# MCU_IO.net
KiCad netlist of a schematic drawn in Altium Designer
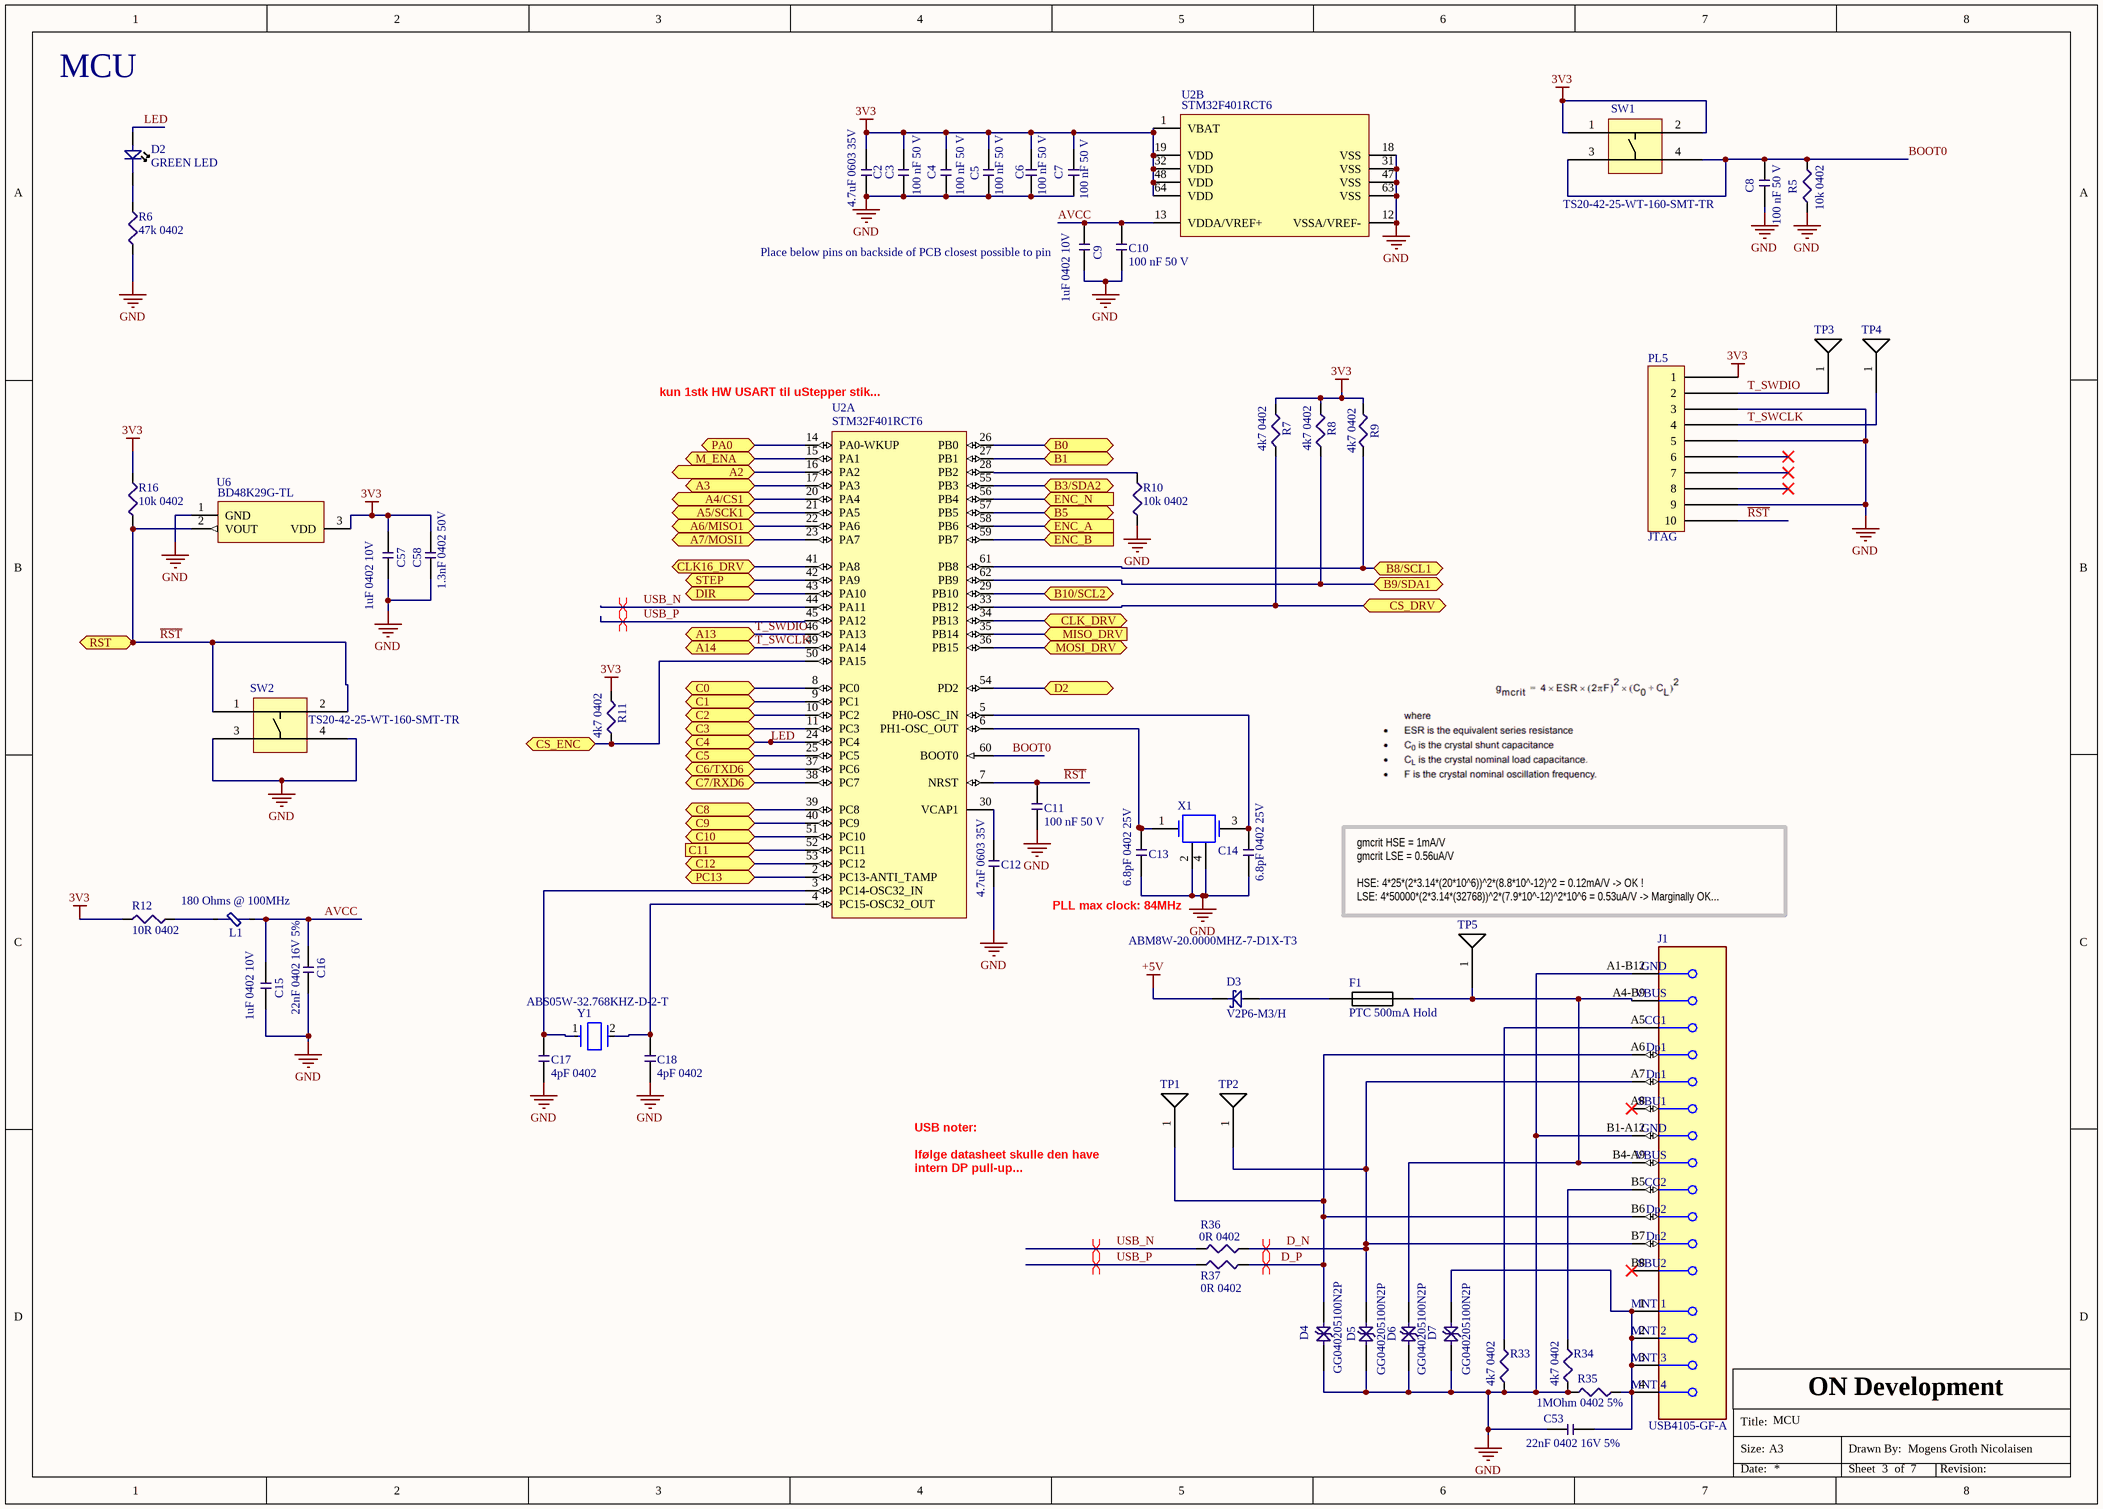
[diagram p0: MCU+IO.SchDoc]

(export (version "E")
  (design (tool "Eeschema 10.0.6"))
  (components
    (comp (ref "C2")
      (value "4.7uF 0603 35V")
      (footprint "CAP_0603")
      (fields (field (name "TOLERANCE") "10%"))
      (libsource (lib "ON Development Vault") (part "Capacitor"))
    )
    (comp (ref "C3")
      (value "100 nF 50 V")
      (footprint "CAP_0402")
      (description "Multilayer Ceramic Capacitors MLCC - SMD/SMT .1uF 50Volts X7R +/-10% 0402 STD")
      (fields (field (name "TOLERANCE") "10%") (field (name "VOLTAGE") "50 V"))
      (libsource (lib "ON Development Vault") (part "Capacitor"))
    )
    (comp (ref "C4")
      (value "100 nF 50 V")
      (footprint "CAP_0402")
      (description "Multilayer Ceramic Capacitors MLCC - SMD/SMT .1uF 50Volts X7R +/-10% 0402 STD")
      (fields (field (name "TOLERANCE") "10%") (field (name "VOLTAGE") "50 V"))
      (libsource (lib "ON Development Vault") (part "Capacitor"))
    )
    (comp (ref "C5")
      (value "100 nF 50 V")
      (footprint "CAP_0402")
      (description "Multilayer Ceramic Capacitors MLCC - SMD/SMT .1uF 50Volts X7R +/-10% 0402 STD")
      (fields (field (name "TOLERANCE") "10%") (field (name "VOLTAGE") "50 V"))
      (libsource (lib "ON Development Vault") (part "Capacitor"))
    )
    (comp (ref "C6")
      (value "100 nF 50 V")
      (footprint "CAP_0402")
      (description "Multilayer Ceramic Capacitors MLCC - SMD/SMT .1uF 50Volts X7R +/-10% 0402 STD")
      (fields (field (name "TOLERANCE") "10%") (field (name "VOLTAGE") "50 V"))
      (libsource (lib "ON Development Vault") (part "Capacitor"))
    )
    (comp (ref "C7")
      (value "100 nF 50 V")
      (footprint "CAP_0402")
      (description "Multilayer Ceramic Capacitors MLCC - SMD/SMT .1uF 50Volts X7R +/-10% 0402 STD")
      (fields (field (name "TOLERANCE") "10%") (field (name "VOLTAGE") "50 V"))
      (libsource (lib "ON Development Vault") (part "Capacitor"))
    )
    (comp (ref "C8")
      (value "100 nF 50 V")
      (footprint "CAP_0402")
      (description "Multilayer Ceramic Capacitors MLCC - SMD/SMT .1uF 50Volts X7R +/-10% 0402 STD")
      (fields (field (name "TOLERANCE") "10%") (field (name "VOLTAGE") "50 V"))
      (libsource (lib "ON Development Vault") (part "Capacitor"))
    )
    (comp (ref "C9")
      (value "1uF 0402 10V")
      (footprint "CAP_0402")
      (description "1uF 0402 10V 10% X5R")
      (fields (field (name "TOLERANCE") "10%") (field (name "VOLTAGE") "10 V"))
      (libsource (lib "ON Development Vault") (part "Capacitor"))
    )
    (comp (ref "C10")
      (value "100 nF 50 V")
      (footprint "CAP_0402")
      (description "Multilayer Ceramic Capacitors MLCC - SMD/SMT .1uF 50Volts X7R +/-10% 0402 STD")
      (fields (field (name "TOLERANCE") "10%") (field (name "VOLTAGE") "50 V"))
      (libsource (lib "ON Development Vault") (part "Capacitor"))
    )
    (comp (ref "C11")
      (value "100 nF 50 V")
      (footprint "CAP_0402")
      (description "Multilayer Ceramic Capacitors MLCC - SMD/SMT .1uF 50Volts X7R +/-10% 0402 STD")
      (fields (field (name "TOLERANCE") "10%") (field (name "VOLTAGE") "50 V"))
      (libsource (lib "ON Development Vault") (part "Capacitor"))
    )
    (comp (ref "C12")
      (value "4.7uF 0603 35V")
      (footprint "CAP_0603")
      (fields (field (name "TOLERANCE") "10%"))
      (libsource (lib "ON Development Vault") (part "Capacitor"))
    )
    (comp (ref "C13")
      (value "6.8pF 0402 25V")
      (footprint "CAP_0402")
      (description "Multilayer Ceramic Capacitors MLCC - SMD/SMT 0402 6.8pF 25volts C0G +/-0.25pF")
      (fields (field (name "VOLTAGE") "25V") (field (name "MANUFACTURER PART NO.") "GRM1555C1E6R8CA01D"))
      (libsource (lib "ON Development Vault") (part "Capacitor"))
    )
    (comp (ref "C14")
      (value "6.8pF 0402 25V")
      (footprint "CAP_0402")
      (description "Multilayer Ceramic Capacitors MLCC - SMD/SMT 0402 6.8pF 25volts C0G +/-0.25pF")
      (fields (field (name "VOLTAGE") "25V") (field (name "MANUFACTURER PART NO.") "GRM1555C1E6R8CA01D"))
      (libsource (lib "ON Development Vault") (part "Capacitor"))
    )
    (comp (ref "C15")
      (value "1uF 0402 10V")
      (footprint "CAP_0402")
      (description "1uF 0402 10V 10% X5R")
      (fields (field (name "TOLERANCE") "10%") (field (name "VOLTAGE") "10 V"))
      (libsource (lib "ON Development Vault") (part "Capacitor"))
    )
    (comp (ref "C16")
      (value "22nF 0402 16V 5%")
      (footprint "CAP_0402")
      (description "22nF 0402 16V X7R 5%")
      (fields (field (name "TOLERANCE") "5%") (field (name "VOLTAGE") "16V"))
      (libsource (lib "ON Development Vault") (part "Capacitor"))
    )
    (comp (ref "C17")
      (value "4pF 0402")
      (footprint "CAP_0402")
      (description "GJM1555C1HR40BB01D ; Rohs; Murata ; Cap Ceramic 0.4PF 50V C0G 0402")
      (fields (field (name "TOLERANCE") "0.1pF") (field (name "VOLTAGE") "50V"))
      (libsource (lib "ON Development Vault") (part "Capacitor"))
    )
    (comp (ref "C18")
      (value "4pF 0402")
      (footprint "CAP_0402")
      (description "GJM1555C1HR40BB01D ; Rohs; Murata ; Cap Ceramic 0.4PF 50V C0G 0402")
      (fields (field (name "TOLERANCE") "0.1pF") (field (name "VOLTAGE") "50V"))
      (libsource (lib "ON Development Vault") (part "Capacitor"))
    )
    (comp (ref "C53")
      (value "22nF 0402 16V 5%")
      (footprint "CAP_0402")
      (description "22nF 0402 16V X7R 5%")
      (fields (field (name "TOLERANCE") "5%") (field (name "VOLTAGE") "16V"))
      (libsource (lib "ON Development Vault") (part "Capacitor"))
    )
    (comp (ref "C57")
      (value "1uF 0402 10V")
      (footprint "CAP_0402")
      (description "1uF 0402 10V 10% X5R")
      (fields (field (name "TOLERANCE") "10%") (field (name "VOLTAGE") "10 V"))
      (libsource (lib "ON Development Vault") (part "Capacitor"))
    )
    (comp (ref "C58")
      (value "1.3nF 0402 50V")
      (footprint "CAP_0402")
      (description "Cap Ceramic 0.0013uF 50V C0G 5% SMD 0402 125°C Paper T/R")
      (fields (field (name "TOLERANCE") "10%") (field (name "VOLTAGE") "50V"))
      (libsource (lib "ON Development Vault") (part "Capacitor"))
    )
    (comp (ref "D2")
      (value "GREEN LED")
      (footprint "0402 LED")
      (description "0402 SMD LED")
      (fields (field (name "MFG. PART NUMBER") "LTST-C281KGKT"))
      (libsource (lib "ON Development Vault") (part "LED"))
    )
    (comp (ref "D3")
      (value "V2P6-M3/H")
      (footprint "MicroSMP")
      (description "DIODE SCHOTTKY 60V 2A MICROSMP")
      (libsource (lib "ON Development Vault") (part "Schottky"))
    )
    (comp (ref "D4")
      (value "TVS")
      (footprint "RES_0402")
      (description "TVS DIODE 12VC 8A IPP 0402")
      (fields (field (name "MFG. PART NUMBER") "GG040205100N2P"))
      (libsource (lib "ON Development Vault") (part "TVS"))
    )
    (comp (ref "D5")
      (value "TVS")
      (footprint "RES_0402")
      (description "TVS DIODE 12VC 8A IPP 0402")
      (fields (field (name "MFG. PART NUMBER") "GG040205100N2P"))
      (libsource (lib "ON Development Vault") (part "TVS"))
    )
    (comp (ref "D6")
      (value "TVS")
      (footprint "RES_0402")
      (description "TVS DIODE 12VC 8A IPP 0402")
      (fields (field (name "MFG. PART NUMBER") "GG040205100N2P"))
      (libsource (lib "ON Development Vault") (part "TVS"))
    )
    (comp (ref "D7")
      (value "TVS")
      (footprint "RES_0402")
      (description "TVS DIODE 12VC 8A IPP 0402")
      (fields (field (name "MFG. PART NUMBER") "GG040205100N2P"))
      (libsource (lib "ON Development Vault") (part "TVS"))
    )
    (comp (ref "F1")
      (value "PTC 500mA Hold")
      (footprint "PTC Fuse 1206")
      (description "PTC RESET FUSE 8V 500MA 1206")
      (fields (field (name "MFG. PART NUMBER") "0ZCJ0050FF2G"))
      (libsource (lib "ON Development Vault") (part "Fuse"))
    )
    (comp (ref "J1")
      (value "USB4105-GF-A")
      (footprint "FP-USB4105-GF-A-MFG")
      (description "Conn USB 2.0 Type C RCP 24 POS 0.3mm/0.5mm Solder RA SMD 24 Terminal 1 Port T/R")
      (libsource (lib "ON Development Vault") (part "e7c17a616881a82b79941196b4bec10"))
    )
    (comp (ref "L1")
      (value "180 Ohms @ 100MHz")
      (footprint "IND_0603")
      (description "FERRITE BEAD 180 OHM 0603 1LN")
      (fields (field (name "MFG. PART NUMBER") "BLM18PG181SN1D"))
      (libsource (lib "ON Development Vault") (part "Ferrite"))
    )
    (comp (ref "PL5")
      (value "JTAG")
      (footprint "FP-62101021021-MFG")
      (description "Conn, Header, 10Pos, 2Row, 1.27Mm Rohs Compliant: Yes")
      (libsource (lib "ON Development Vault") (part "10-pin header"))
    )
    (comp (ref "R5")
      (value "10k 0402")
      (footprint "RES_0402")
      (description "RES SMD 10K OHM 1% 1/16W 0402")
      (fields (field (name "POWER") "1/16 W") (field (name "TOLERANCE") "1 %"))
      (libsource (lib "ON Development Vault") (part "Resistor"))
    )
    (comp (ref "R6")
      (value "47k 0402")
      (footprint "RES_0402")
      (description "RES SMD 47K OHM 1% 1/16W 0402")
      (fields (field (name "POWER") "1/16W") (field (name "TOLERANCE") "1%"))
      (libsource (lib "ON Development Vault") (part "Resistor"))
    )
    (comp (ref "R7")
      (value "4k7 0402")
      (footprint "RES_0402")
      (description "RES SMD 4.7K OHM 1% 1/16W 0402")
      (fields (field (name "POWER") "1/16W") (field (name "TOLERANCE") "1"))
      (libsource (lib "ON Development Vault") (part "Resistor"))
    )
    (comp (ref "R8")
      (value "4k7 0402")
      (footprint "RES_0402")
      (description "RES SMD 4.7K OHM 1% 1/16W 0402")
      (fields (field (name "POWER") "1/16W") (field (name "TOLERANCE") "1"))
      (libsource (lib "ON Development Vault") (part "Resistor"))
    )
    (comp (ref "R9")
      (value "4k7 0402")
      (footprint "RES_0402")
      (description "RES SMD 4.7K OHM 1% 1/16W 0402")
      (fields (field (name "POWER") "1/16W") (field (name "TOLERANCE") "1"))
      (libsource (lib "ON Development Vault") (part "Resistor"))
    )
    (comp (ref "R10")
      (value "10k 0402")
      (footprint "RES_0402")
      (description "RES SMD 10K OHM 1% 1/16W 0402")
      (fields (field (name "POWER") "1/16 W") (field (name "TOLERANCE") "1 %"))
      (libsource (lib "ON Development Vault") (part "Resistor"))
    )
    (comp (ref "R11")
      (value "4k7 0402")
      (footprint "RES_0402")
      (description "RES SMD 4.7K OHM 1% 1/16W 0402")
      (fields (field (name "POWER") "1/16W") (field (name "TOLERANCE") "1"))
      (libsource (lib "ON Development Vault") (part "Resistor"))
    )
    (comp (ref "R12")
      (value "10R 0402")
      (footprint "RES_0402")
      (description "RES SMD 10 OHM 1% 1/16W 0402")
      (fields (field (name "POWER") "63mW") (field (name "TOLERANCE") "1%"))
      (libsource (lib "ON Development Vault") (part "Resistor"))
    )
    (comp (ref "R16")
      (value "10k 0402")
      (footprint "RES_0402")
      (description "RES SMD 10K OHM 1% 1/16W 0402")
      (fields (field (name "POWER") "1/16 W") (field (name "TOLERANCE") "1 %"))
      (libsource (lib "ON Development Vault") (part "Resistor"))
    )
    (comp (ref "R33")
      (value "4k7 0402")
      (footprint "RES_0402")
      (description "RES SMD 4.7K OHM 1% 1/16W 0402")
      (fields (field (name "POWER") "1/16W") (field (name "TOLERANCE") "1"))
      (libsource (lib "ON Development Vault") (part "Resistor"))
    )
    (comp (ref "R34")
      (value "4k7 0402")
      (footprint "RES_0402")
      (description "RES SMD 4.7K OHM 1% 1/16W 0402")
      (fields (field (name "POWER") "1/16W") (field (name "TOLERANCE") "1"))
      (libsource (lib "ON Development Vault") (part "Resistor"))
    )
    (comp (ref "R35")
      (value "1MOhm 0402 5%")
      (footprint "RES_0402")
      (description "RES SMD 1M OHM 5% 1/16W 0402")
      (fields (field (name "POWER") "1/16 W") (field (name "TOLERANCE") "5%"))
      (libsource (lib "ON Development Vault") (part "Resistor"))
    )
    (comp (ref "R36")
      (value "0R 0402")
      (footprint "RES_0402")
      (description "RES SMD 0 OHM 1/16W 0402")
      (fields (field (name "POWER") "63mW") (field (name "MFG. PART NUMBER") "RC0402JR-070RL"))
      (libsource (lib "ON Development Vault") (part "Resistor"))
    )
    (comp (ref "R37")
      (value "0R 0402")
      (footprint "RES_0402")
      (description "RES SMD 0 OHM 1/16W 0402")
      (fields (field (name "POWER") "63mW") (field (name "MFG. PART NUMBER") "RC0402JR-070RL"))
      (libsource (lib "ON Development Vault") (part "Resistor"))
    )
    (comp (ref "SW1")
      (value "TS20-42-25-WT-160-SMT-TR")
      (footprint "TS20-42-25-WT-160-SMT-TR-Footprint-1")
      (description "Tactile Switch SPST-NO Top Actuated Surface Mount")
      (libsource (lib "ON Development Vault") (part "PTS540"))
    )
    (comp (ref "SW2")
      (value "TS20-42-25-WT-160-SMT-TR")
      (footprint "TS20-42-25-WT-160-SMT-TR-Footprint-1")
      (description "Tactile Switch SPST-NO Top Actuated Surface Mount")
      (libsource (lib "ON Development Vault") (part "PTS540"))
    )
    (comp (ref "TP1")
      (value "TestPoint")
      (footprint "1x0mm")
      (description "Testpoint")
      (libsource (lib "ON Development Vault") (part "Testpoint"))
    )
    (comp (ref "TP2")
      (value "TestPoint")
      (footprint "1x0mm")
      (description "Testpoint")
      (libsource (lib "ON Development Vault") (part "Testpoint"))
    )
    (comp (ref "TP3")
      (value "TestPoint")
      (footprint "1x0mm")
      (description "Testpoint")
      (libsource (lib "ON Development Vault") (part "Testpoint"))
    )
    (comp (ref "TP4")
      (value "TestPoint")
      (footprint "1x0mm")
      (description "Testpoint")
      (libsource (lib "ON Development Vault") (part "Testpoint"))
    )
    (comp (ref "TP5")
      (value "TestPoint")
      (footprint "1x0mm")
      (description "Testpoint")
      (libsource (lib "ON Development Vault") (part "Testpoint"))
    )
    (comp (ref "U2")
      (value "STM32F401RCT6")
      (footprint "STM-LQFP64_M")
      (description "ARM® Cortex®-M4 STM32 F4 Microcontroller IC 32-Bit 84MHz 256KB (256K x 8) FLASH")
      (libsource (lib "ON Development Vault") (part "MC-ARM-STM32F401-SQ64"))
    )
    (comp (ref "U6")
      (value "Supervisor")
      (footprint "SOT95P282X125-3N")
      (description "IC DETECTOR VOLT 2.9V OD SSOP3")
      (fields (field (name "MANUFACTURER PART NO.:") "BD48K29G-TL"))
      (libsource (lib "ON Development Vault") (part "BD48K29G-TL-Symbol-1"))
    )
    (comp (ref "X1")
      (value "ABM8W-20.0000MHZ-7-D1X-T3")
      (footprint "3.2x2.5mm 4pin xtal")
      (description "Crystal 20MHz ±10ppm (Tol) ±20ppm (Stability) 7pF FUND 50Ohm 4-Pin SMD T/R")
      (libsource (lib "ON Development Vault") (part "TSX-3225 20MHZ"))
    )
    (comp (ref "Y1")
      (value "ABS05W-32.768KHZ-D-2-T")
      (footprint "FP-ABS05W-MFG")
      (description "ABS05W IoT Optimized Crystal 32.768KHz 4pF 70K Ohm ±20ppm 2-Pin SMD T/R")
      (libsource (lib "ON Development Vault") (part "c23a69dc6c9e2f18f2079038eb95dd1"))
    )
  )
  (nets
    (net (code "1") (name "+5V") (class "Default")
      (node (ref "D3") (pin "2") (pinfunction "2_2") (pintype "passive"))
    )
    (net (code "2") (name "/A2") (class "Default")
      (node (ref "U2") (pin "16") (pinfunction "PA2_16") (pintype "bidirectional"))
    )
    (net (code "3") (name "/A3") (class "Default")
      (node (ref "U2") (pin "17") (pinfunction "PA3_17") (pintype "bidirectional"))
    )
    (net (code "4") (name "/A4{slash}CS1") (class "Default")
      (node (ref "U2") (pin "20") (pinfunction "PA4_20") (pintype "bidirectional"))
    )
    (net (code "5") (name "/A5{slash}SCK1") (class "Default")
      (node (ref "U2") (pin "21") (pinfunction "PA5_21") (pintype "bidirectional"))
    )
    (net (code "6") (name "/A6{slash}MISO1") (class "Default")
      (node (ref "U2") (pin "22") (pinfunction "PA6_22") (pintype "bidirectional"))
    )
    (net (code "7") (name "/A7{slash}MOSI1") (class "Default")
      (node (ref "U2") (pin "23") (pinfunction "PA7_23") (pintype "bidirectional"))
    )
    (net (code "8") (name "/AVCC") (class "Default")
      (node (ref "C10") (pin "2") (pinfunction "2_2") (pintype "passive"))
      (node (ref "C15") (pin "2") (pinfunction "2_2") (pintype "passive"))
      (node (ref "C16") (pin "2") (pinfunction "2_2") (pintype "passive"))
      (node (ref "C9") (pin "2") (pinfunction "2_2") (pintype "passive"))
      (node (ref "L1") (pin "2") (pinfunction "2_2") (pintype "passive"))
      (node (ref "U2") (pin "13") (pinfunction "VDDA/VREF+_13") (pintype "power_in"))
    )
    (net (code "9") (name "/B0") (class "Default")
      (node (ref "U2") (pin "26") (pinfunction "PB0_26") (pintype "bidirectional"))
    )
    (net (code "10") (name "/B1") (class "Default")
      (node (ref "U2") (pin "27") (pinfunction "PB1_27") (pintype "bidirectional"))
    )
    (net (code "11") (name "/B3{slash}SDA2") (class "Default")
      (node (ref "U2") (pin "55") (pinfunction "PB3_55") (pintype "bidirectional"))
    )
    (net (code "12") (name "/B5") (class "Default")
      (node (ref "U2") (pin "57") (pinfunction "PB5_57") (pintype "bidirectional"))
    )
    (net (code "13") (name "/B8{slash}SCL1") (class "Default")
      (node (ref "R9") (pin "1") (pinfunction "1_1") (pintype "passive"))
      (node (ref "U2") (pin "61") (pinfunction "PB8_61") (pintype "bidirectional"))
    )
    (net (code "14") (name "/B9{slash}SDA1") (class "Default")
      (node (ref "R8") (pin "1") (pinfunction "1_1") (pintype "passive"))
      (node (ref "U2") (pin "62") (pinfunction "PB9_62") (pintype "bidirectional"))
    )
    (net (code "15") (name "/B10{slash}SCL2") (class "Default")
      (node (ref "U2") (pin "29") (pinfunction "PB10_29") (pintype "bidirectional"))
    )
    (net (code "16") (name "/BOOT0") (class "Default")
      (node (ref "C8") (pin "2") (pinfunction "2_2") (pintype "passive"))
      (node (ref "R5") (pin "2") (pinfunction "2_2") (pintype "passive"))
      (node (ref "SW1") (pin "3") (pinfunction "3_3") (pintype "passive"))
      (node (ref "SW1") (pin "4") (pinfunction "4_4") (pintype "passive"))
      (node (ref "U2") (pin "60") (pinfunction "BOOT0_60") (pintype "input"))
    )
    (net (code "17") (name "/C0") (class "Default")
      (node (ref "U2") (pin "8") (pinfunction "PC0_8") (pintype "bidirectional"))
    )
    (net (code "18") (name "/C1") (class "Default")
      (node (ref "U2") (pin "9") (pinfunction "PC1_9") (pintype "bidirectional"))
    )
    (net (code "19") (name "/C2") (class "Default")
      (node (ref "U2") (pin "10") (pinfunction "PC2_10") (pintype "bidirectional"))
    )
    (net (code "20") (name "/C3") (class "Default")
      (node (ref "U2") (pin "11") (pinfunction "PC3_11") (pintype "bidirectional"))
    )
    (net (code "21") (name "/C5") (class "Default")
      (node (ref "U2") (pin "25") (pinfunction "PC5_25") (pintype "bidirectional"))
    )
    (net (code "22") (name "/C6{slash}TXD6") (class "Default")
      (node (ref "U2") (pin "37") (pinfunction "PC6_37") (pintype "bidirectional"))
    )
    (net (code "23") (name "/C7{slash}RXD6") (class "Default")
      (node (ref "U2") (pin "38") (pinfunction "PC7_38") (pintype "bidirectional"))
    )
    (net (code "24") (name "/C8") (class "Default")
      (node (ref "U2") (pin "39") (pinfunction "PC8_39") (pintype "bidirectional"))
    )
    (net (code "25") (name "/C9") (class "Default")
      (node (ref "U2") (pin "40") (pinfunction "PC9_40") (pintype "bidirectional"))
    )
    (net (code "26") (name "/C10") (class "Default")
      (node (ref "U2") (pin "51") (pinfunction "PC10_51") (pintype "bidirectional"))
    )
    (net (code "27") (name "/C11") (class "Default")
      (node (ref "U2") (pin "52") (pinfunction "PC11_52") (pintype "bidirectional"))
    )
    (net (code "28") (name "/C12") (class "Default")
      (node (ref "U2") (pin "53") (pinfunction "PC12_53") (pintype "bidirectional"))
    )
    (net (code "29") (name "/CLK16_DRV") (class "Default")
      (node (ref "U2") (pin "41") (pinfunction "PA8_41") (pintype "bidirectional"))
    )
    (net (code "30") (name "/CLK_DRV") (class "Default")
      (node (ref "U2") (pin "34") (pinfunction "PB13_34") (pintype "bidirectional"))
    )
    (net (code "31") (name "/CS_DRV") (class "Default")
      (node (ref "R7") (pin "1") (pinfunction "1_1") (pintype "passive"))
      (node (ref "U2") (pin "33") (pinfunction "PB12_33") (pintype "bidirectional"))
    )
    (net (code "32") (name "/CS_ENC") (class "Default")
      (node (ref "R11") (pin "1") (pinfunction "1_1") (pintype "passive"))
      (node (ref "U2") (pin "50") (pinfunction "PA15_50") (pintype "bidirectional"))
    )
    (net (code "33") (name "/D2") (class "Default")
      (node (ref "U2") (pin "54") (pinfunction "PD2_54") (pintype "bidirectional"))
    )
    (net (code "34") (name "/DIR") (class "Default")
      (node (ref "U2") (pin "43") (pinfunction "PA10_43") (pintype "bidirectional"))
    )
    (net (code "35") (name "/D_N") (class "Default")
      (node (ref "D5") (pin "2") (pinfunction "Cathode_2") (pintype "passive"))
      (node (ref "J1") (pin "A7") (pinfunction "Dn1_A7") (pintype "bidirectional"))
      (node (ref "J1") (pin "B7") (pinfunction "Dn2_B7") (pintype "bidirectional"))
      (node (ref "R36") (pin "2") (pinfunction "2_2") (pintype "passive"))
      (node (ref "TP2") (pin "1") (pinfunction "0_1") (pintype "passive"))
    )
    (net (code "36") (name "/D_P") (class "Default")
      (node (ref "D4") (pin "2") (pinfunction "Cathode_2") (pintype "passive"))
      (node (ref "J1") (pin "A6") (pinfunction "Dp1_A6") (pintype "bidirectional"))
      (node (ref "J1") (pin "B6") (pinfunction "Dp2_B6") (pintype "bidirectional"))
      (node (ref "R37") (pin "2") (pinfunction "2_2") (pintype "passive"))
      (node (ref "TP1") (pin "1") (pinfunction "0_1") (pintype "passive"))
    )
    (net (code "37") (name "/ENC_A") (class "Default")
      (node (ref "U2") (pin "58") (pinfunction "PB6_58") (pintype "bidirectional"))
    )
    (net (code "38") (name "/ENC_B") (class "Default")
      (node (ref "U2") (pin "59") (pinfunction "PB7_59") (pintype "bidirectional"))
    )
    (net (code "39") (name "/ENC_N") (class "Default")
      (node (ref "U2") (pin "56") (pinfunction "PB4_56") (pintype "bidirectional"))
    )
    (net (code "40") (name "/LED") (class "Default")
      (node (ref "D2") (pin "1") (pinfunction "1_1") (pintype "passive"))
      (node (ref "U2") (pin "24") (pinfunction "PC4_24") (pintype "bidirectional"))
    )
    (net (code "41") (name "/MISO_DRV") (class "Default")
      (node (ref "U2") (pin "35") (pinfunction "PB14_35") (pintype "bidirectional"))
    )
    (net (code "42") (name "/MOSI_DRV") (class "Default")
      (node (ref "U2") (pin "36") (pinfunction "PB15_36") (pintype "bidirectional"))
    )
    (net (code "43") (name "/M_ENA") (class "Default")
      (node (ref "U2") (pin "15") (pinfunction "PA1_15") (pintype "bidirectional"))
    )
    (net (code "44") (name "/PA0") (class "Default")
      (node (ref "U2") (pin "14") (pinfunction "PA0-WKUP_14") (pintype "bidirectional"))
    )
    (net (code "45") (name "/PC13") (class "Default")
      (node (ref "U2") (pin "2") (pinfunction "PC13-ANTI_TAMP_2") (pintype "bidirectional"))
    )
    (net (code "46") (name "/STEP") (class "Default")
      (node (ref "U2") (pin "42") (pinfunction "PA9_42") (pintype "bidirectional"))
    )
    (net (code "47") (name "/T_SWCLK") (class "Default")
      (node (ref "PL5") (pin "4") (pinfunction "4_4") (pintype "passive"))
      (node (ref "TP4") (pin "1") (pinfunction "0_1") (pintype "passive"))
      (node (ref "U2") (pin "49") (pinfunction "PA14_49") (pintype "bidirectional"))
    )
    (net (code "48") (name "/T_SWDIO") (class "Default")
      (node (ref "PL5") (pin "2") (pinfunction "2_2") (pintype "passive"))
      (node (ref "TP3") (pin "1") (pinfunction "0_1") (pintype "passive"))
      (node (ref "U2") (pin "46") (pinfunction "PA13_46") (pintype "bidirectional"))
    )
    (net (code "49") (name "/USB_N") (class "Default")
      (node (ref "R36") (pin "1") (pinfunction "1_1") (pintype "passive"))
      (node (ref "U2") (pin "44") (pinfunction "PA11_44") (pintype "bidirectional"))
    )
    (net (code "50") (name "/USB_P") (class "Default")
      (node (ref "R37") (pin "1") (pinfunction "1_1") (pintype "passive"))
      (node (ref "U2") (pin "45") (pinfunction "PA12_45") (pintype "bidirectional"))
    )
    (net (code "51") (name "/~{RST}") (class "Default")
      (node (ref "C11") (pin "2") (pinfunction "2_2") (pintype "passive"))
      (node (ref "PL5") (pin "10") (pinfunction "10_10") (pintype "passive"))
      (node (ref "R16") (pin "1") (pinfunction "1_1") (pintype "passive"))
      (node (ref "SW2") (pin "1") (pinfunction "1_1") (pintype "passive"))
      (node (ref "SW2") (pin "2") (pinfunction "2_2") (pintype "passive"))
      (node (ref "U2") (pin "7") (pinfunction "NRST_7") (pintype "bidirectional"))
      (node (ref "U6") (pin "2") (pinfunction "VOUT_2") (pintype "output"))
    )
    (net (code "52") (name "3V3") (class "Default")
      (node (ref "C2") (pin "2") (pinfunction "2_2") (pintype "passive"))
      (node (ref "C3") (pin "2") (pinfunction "2_2") (pintype "passive"))
      (node (ref "C4") (pin "2") (pinfunction "2_2") (pintype "passive"))
      (node (ref "C5") (pin "2") (pinfunction "2_2") (pintype "passive"))
      (node (ref "C57") (pin "2") (pinfunction "2_2") (pintype "passive"))
      (node (ref "C58") (pin "2") (pinfunction "2_2") (pintype "passive"))
      (node (ref "C6") (pin "2") (pinfunction "2_2") (pintype "passive"))
      (node (ref "C7") (pin "2") (pinfunction "2_2") (pintype "passive"))
      (node (ref "PL5") (pin "1") (pinfunction "1_1") (pintype "passive"))
      (node (ref "R11") (pin "2") (pinfunction "2_2") (pintype "passive"))
      (node (ref "R12") (pin "1") (pinfunction "1_1") (pintype "passive"))
      (node (ref "R16") (pin "2") (pinfunction "2_2") (pintype "passive"))
      (node (ref "R7") (pin "2") (pinfunction "2_2") (pintype "passive"))
      (node (ref "R8") (pin "2") (pinfunction "2_2") (pintype "passive"))
      (node (ref "R9") (pin "2") (pinfunction "2_2") (pintype "passive"))
      (node (ref "SW1") (pin "1") (pinfunction "1_1") (pintype "passive"))
      (node (ref "SW1") (pin "2") (pinfunction "2_2") (pintype "passive"))
      (node (ref "U2") (pin "1") (pinfunction "VBAT_1") (pintype "power_in"))
      (node (ref "U2") (pin "19") (pinfunction "VDD_19") (pintype "power_in"))
      (node (ref "U2") (pin "32") (pinfunction "VDD_32") (pintype "power_in"))
      (node (ref "U2") (pin "48") (pinfunction "VDD_48") (pintype "power_in"))
      (node (ref "U2") (pin "64") (pinfunction "VDD_64") (pintype "power_in"))
      (node (ref "U6") (pin "3") (pinfunction "VDD_3") (pintype "power_in"))
    )
    (net (code "53") (name "GND") (class "Default")
      (node (ref "C10") (pin "1") (pinfunction "1_1") (pintype "passive"))
      (node (ref "C11") (pin "1") (pinfunction "1_1") (pintype "passive"))
      (node (ref "C12") (pin "1") (pinfunction "1_1") (pintype "passive"))
      (node (ref "C13") (pin "1") (pinfunction "1_1") (pintype "passive"))
      (node (ref "C14") (pin "1") (pinfunction "1_1") (pintype "passive"))
      (node (ref "C15") (pin "1") (pinfunction "1_1") (pintype "passive"))
      (node (ref "C16") (pin "1") (pinfunction "1_1") (pintype "passive"))
      (node (ref "C17") (pin "1") (pinfunction "1_1") (pintype "passive"))
      (node (ref "C18") (pin "1") (pinfunction "1_1") (pintype "passive"))
      (node (ref "C2") (pin "1") (pinfunction "1_1") (pintype "passive"))
      (node (ref "C3") (pin "1") (pinfunction "1_1") (pintype "passive"))
      (node (ref "C4") (pin "1") (pinfunction "1_1") (pintype "passive"))
      (node (ref "C5") (pin "1") (pinfunction "1_1") (pintype "passive"))
      (node (ref "C53") (pin "1") (pinfunction "1_1") (pintype "passive"))
      (node (ref "C57") (pin "1") (pinfunction "1_1") (pintype "passive"))
      (node (ref "C58") (pin "1") (pinfunction "1_1") (pintype "passive"))
      (node (ref "C6") (pin "1") (pinfunction "1_1") (pintype "passive"))
      (node (ref "C7") (pin "1") (pinfunction "1_1") (pintype "passive"))
      (node (ref "C8") (pin "1") (pinfunction "1_1") (pintype "passive"))
      (node (ref "C9") (pin "1") (pinfunction "1_1") (pintype "passive"))
      (node (ref "D4") (pin "1") (pinfunction "Anode_1") (pintype "passive"))
      (node (ref "D5") (pin "1") (pinfunction "Anode_1") (pintype "passive"))
      (node (ref "D6") (pin "1") (pinfunction "Anode_1") (pintype "passive"))
      (node (ref "D7") (pin "1") (pinfunction "Anode_1") (pintype "passive"))
      (node (ref "J1") (pin "A1-B12") (pinfunction "GND_A1-B12") (pintype "power_in"))
      (node (ref "J1") (pin "B1-A12") (pinfunction "GND_B1-A12") (pintype "bidirectional"))
      (node (ref "PL5") (pin "3") (pinfunction "3_3") (pintype "passive"))
      (node (ref "PL5") (pin "5") (pinfunction "5_5") (pintype "passive"))
      (node (ref "PL5") (pin "9") (pinfunction "9_9") (pintype "passive"))
      (node (ref "R10") (pin "1") (pinfunction "1_1") (pintype "passive"))
      (node (ref "R33") (pin "1") (pinfunction "1_1") (pintype "passive"))
      (node (ref "R34") (pin "1") (pinfunction "1_1") (pintype "passive"))
      (node (ref "R35") (pin "1") (pinfunction "1_1") (pintype "passive"))
      (node (ref "R5") (pin "1") (pinfunction "1_1") (pintype "passive"))
      (node (ref "R6") (pin "1") (pinfunction "1_1") (pintype "passive"))
      (node (ref "SW2") (pin "3") (pinfunction "3_3") (pintype "passive"))
      (node (ref "SW2") (pin "4") (pinfunction "4_4") (pintype "passive"))
      (node (ref "U2") (pin "12") (pinfunction "VSSA/VREF-_12") (pintype "power_in"))
      (node (ref "U2") (pin "18") (pinfunction "VSS_18") (pintype "power_in"))
      (node (ref "U2") (pin "31") (pinfunction "VSS_31") (pintype "power_in"))
      (node (ref "U2") (pin "47") (pinfunction "VSS_47") (pintype "power_in"))
      (node (ref "U2") (pin "63") (pinfunction "VSS_63") (pintype "power_in"))
      (node (ref "U6") (pin "1") (pinfunction "GND_1") (pintype "power_in"))
      (node (ref "X1") (pin "2") (pinfunction "OSC2_2") (pintype "passive"))
      (node (ref "X1") (pin "4") (pinfunction "OSC2_4") (pintype "passive"))
    )
    (net (code "54") (name "Net-(D2-Pad2)") (class "Default")
      (node (ref "D2") (pin "2") (pinfunction "2_2") (pintype "passive"))
      (node (ref "R6") (pin "2") (pinfunction "2_2") (pintype "passive"))
    )
    (net (code "55") (name "Net-(D3-Pad1)") (class "Default")
      (node (ref "D3") (pin "1") (pinfunction "1_1") (pintype "passive"))
      (node (ref "F1") (pin "1") (pinfunction "1_1") (pintype "passive"))
    )
    (net (code "56") (name "Net-(D6-Cathode)") (class "Default")
      (node (ref "D6") (pin "2") (pinfunction "Cathode_2") (pintype "passive"))
      (node (ref "F1") (pin "2") (pinfunction "2_2") (pintype "passive"))
      (node (ref "J1") (pin "A4-B9") (pinfunction "VBUS_A4-B9") (pintype "power_in"))
      (node (ref "J1") (pin "B4-A9") (pinfunction "VBUS_B4-A9") (pintype "bidirectional"))
      (node (ref "TP5") (pin "1") (pinfunction "0_1") (pintype "passive"))
    )
    (net (code "57") (name "Net-(D7-Cathode)") (class "Default")
      (node (ref "C53") (pin "2") (pinfunction "2_2") (pintype "passive"))
      (node (ref "D7") (pin "2") (pinfunction "Cathode_2") (pintype "passive"))
      (node (ref "J1") (pin "1") (pinfunction "MNT_1_1") (pintype "power_in"))
      (node (ref "J1") (pin "2") (pinfunction "MNT_2_2") (pintype "power_in"))
      (node (ref "J1") (pin "3") (pinfunction "MNT_3_3") (pintype "power_in"))
      (node (ref "J1") (pin "4") (pinfunction "MNT_4_4") (pintype "power_in"))
      (node (ref "R35") (pin "2") (pinfunction "2_2") (pintype "passive"))
    )
    (net (code "58") (name "Net-(J1-CC1)") (class "Default")
      (node (ref "J1") (pin "A5") (pinfunction "CC1_A5") (pintype "power_in"))
      (node (ref "R33") (pin "2") (pinfunction "2_2") (pintype "passive"))
    )
    (net (code "59") (name "Net-(J1-CC2)") (class "Default")
      (node (ref "J1") (pin "B5") (pinfunction "CC2_B5") (pintype "bidirectional"))
      (node (ref "R34") (pin "2") (pinfunction "2_2") (pintype "passive"))
    )
    (net (code "60") (name "Net-(L1-Pad1)") (class "Default")
      (node (ref "L1") (pin "1") (pinfunction "1_1") (pintype "passive"))
      (node (ref "R12") (pin "2") (pinfunction "2_2") (pintype "passive"))
    )
    (net (code "61") (name "Net-(U2A-PB2)") (class "Default")
      (node (ref "R10") (pin "2") (pinfunction "2_2") (pintype "passive"))
      (node (ref "U2") (pin "28") (pinfunction "PB2_28") (pintype "bidirectional"))
    )
    (net (code "62") (name "Net-(U2A-PC14-OSC32_IN)") (class "Default")
      (node (ref "C17") (pin "2") (pinfunction "2_2") (pintype "passive"))
      (node (ref "U2") (pin "3") (pinfunction "PC14-OSC32_IN_3") (pintype "bidirectional"))
      (node (ref "Y1") (pin "1") (pinfunction "1_1") (pintype "passive"))
    )
    (net (code "63") (name "Net-(U2A-PC15-OSC32_OUT)") (class "Default")
      (node (ref "C18") (pin "2") (pinfunction "2_2") (pintype "passive"))
      (node (ref "U2") (pin "4") (pinfunction "PC15-OSC32_OUT_4") (pintype "bidirectional"))
      (node (ref "Y1") (pin "2") (pinfunction "2_2") (pintype "passive"))
    )
    (net (code "64") (name "Net-(U2A-PH0-OSC_IN)") (class "Default")
      (node (ref "C14") (pin "2") (pinfunction "2_2") (pintype "passive"))
      (node (ref "U2") (pin "5") (pinfunction "PH0-OSC_IN_5") (pintype "bidirectional"))
      (node (ref "X1") (pin "3") (pinfunction "OSC2_3") (pintype "passive"))
    )
    (net (code "65") (name "Net-(U2A-PH1-OSC_OUT)") (class "Default")
      (node (ref "C13") (pin "2") (pinfunction "2_2") (pintype "passive"))
      (node (ref "U2") (pin "6") (pinfunction "PH1-OSC_OUT_6") (pintype "bidirectional"))
      (node (ref "X1") (pin "1") (pinfunction "OSC1_1") (pintype "passive"))
    )
    (net (code "66") (name "Net-(U2A-VCAP1)") (class "Default")
      (node (ref "C12") (pin "2") (pinfunction "2_2") (pintype "passive"))
      (node (ref "U2") (pin "30") (pinfunction "VCAP1_30") (pintype "power_in"))
    )
    (net (code "67") (name "unconnected-(J1-SBU1-PadA8)") (class "Default")
      (node (ref "J1") (pin "A8") (pinfunction "SBU1_A8") (pintype "bidirectional+no_connect"))
    )
    (net (code "68") (name "unconnected-(J1-SBU2-PadB8)") (class "Default")
      (node (ref "J1") (pin "B8") (pinfunction "SBU2_B8") (pintype "power_in+no_connect"))
    )
    (net (code "69") (name "unconnected-(PL5-Pad6)") (class "Default")
      (node (ref "PL5") (pin "6") (pinfunction "6_6") (pintype "passive+no_connect"))
    )
    (net (code "70") (name "unconnected-(PL5-Pad7)") (class "Default")
      (node (ref "PL5") (pin "7") (pinfunction "7_7") (pintype "passive+no_connect"))
    )
    (net (code "71") (name "unconnected-(PL5-Pad8)") (class "Default")
      (node (ref "PL5") (pin "8") (pinfunction "8_8") (pintype "passive+no_connect"))
    )
  )
)
